# Power.net
KiCad netlist of a schematic drawn in Altium Designer
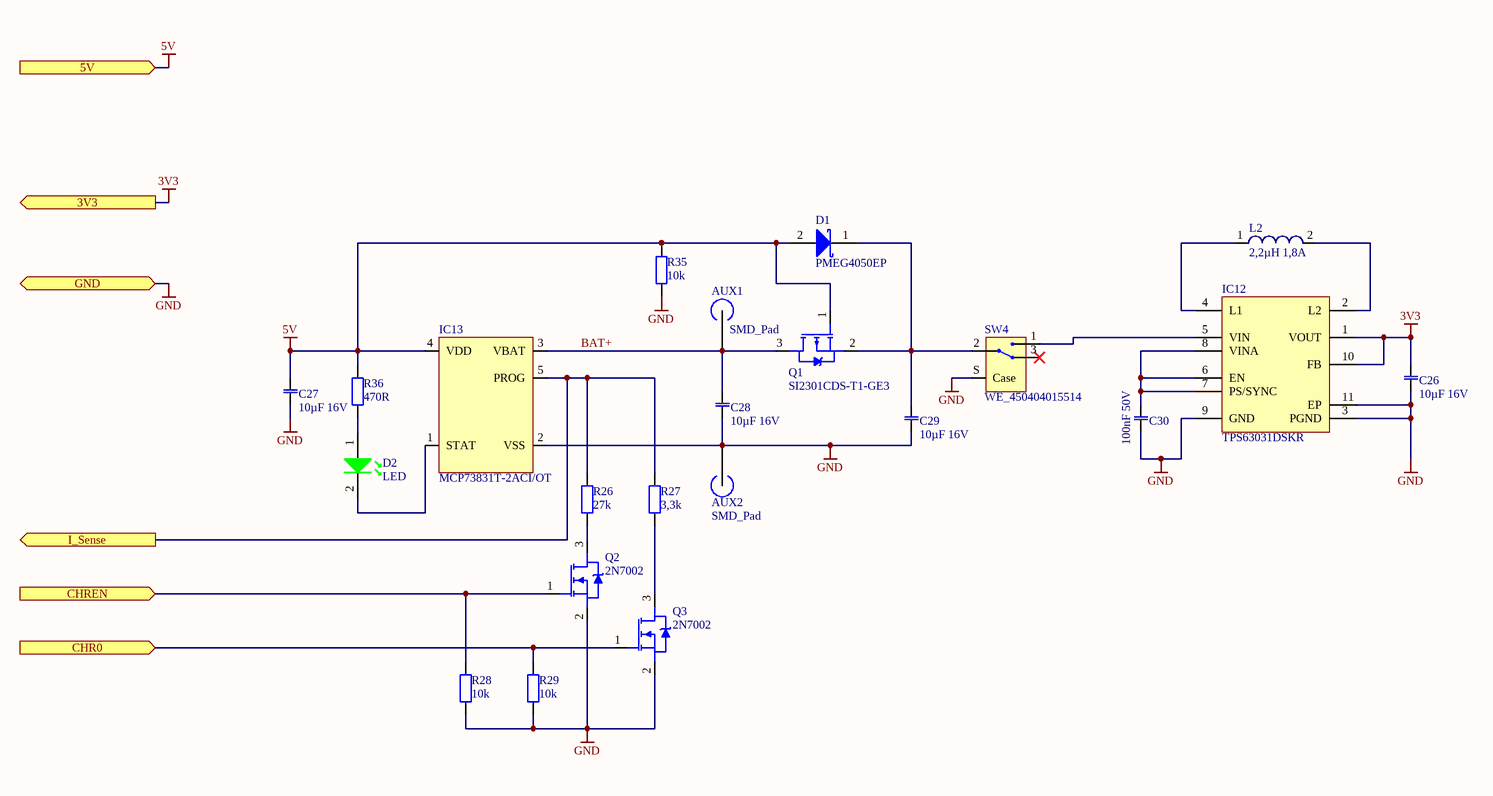
[diagram p0: Power.SchDoc]

(export (version "E")
  (design (tool "Eeschema 10.0.6"))
  (components
    (comp (ref "AUX1")
      (value "SMD_Pad")
      (footprint "SMD_PAD")
      (libsource (lib "iMAR Workspace") (part "AUX1"))
    )
    (comp (ref "AUX2")
      (value "SMD_Pad")
      (footprint "SMD_PAD")
      (libsource (lib "iMAR Workspace") (part "AUX1"))
    )
    (comp (ref "C26")
      (value "10µF 16V")
      (footprint "CAPC1608L")
      (description "10µF  16V  Ceramic  0603  10%  X5R")
      (fields (field (name "TOLERANCE") "10%") (field (name "MANUFACTURER") "unspecified"))
      (libsource (lib "iMAR Workspace") (part "Kondensator"))
    )
    (comp (ref "C27")
      (value "10µF 16V")
      (footprint "CAPC1608L")
      (description "10µF  16V  Ceramic  0603  10%  X5R")
      (fields (field (name "TOLERANCE") "10%") (field (name "MANUFACTURER") "unspecified"))
      (libsource (lib "iMAR Workspace") (part "Kondensator"))
    )
    (comp (ref "C28")
      (value "10µF 16V")
      (footprint "CAPC1608L")
      (description "10µF  16V  Ceramic  0603  10%  X5R")
      (fields (field (name "TOLERANCE") "10%") (field (name "MANUFACTURER") "unspecified"))
      (libsource (lib "iMAR Workspace") (part "Kondensator"))
    )
    (comp (ref "C29")
      (value "10µF 16V")
      (footprint "CAPC1608L")
      (description "10µF  16V  Ceramic  0603  10%  X5R")
      (fields (field (name "TOLERANCE") "10%") (field (name "MANUFACTURER") "unspecified"))
      (libsource (lib "iMAR Workspace") (part "Kondensator"))
    )
    (comp (ref "C30")
      (value "100nF 50V")
      (footprint "CAPC1005N")
      (description "100nF  50V  Ceramic  0402  10%  X7R")
      (fields (field (name "VOLTAGE") "50V") (field (name "MANUFACTURER") "unspecified"))
      (libsource (lib "iMAR Workspace") (part "Kondensator"))
    )
    (comp (ref "D1")
      (value "PMEG4050EP")
      (footprint "SOD4725X110")
      (description "Schottky-Diode 5A low Vf")
      (fields (field (name "MANUFACTURER") "NEXPERIA") (field (name "POWER") "625mW"))
      (libsource (lib "iMAR Workspace") (part "Schottky, A{colon}2, K{colon}1"))
    )
    (comp (ref "D2")
      (value "LED")
      (footprint "LEDM1608X11_Green")
      (description "LED green 0603 2,2V 20mA")
      (fields (field (name "MANUFACTURER") "KINGBRIGHT") (field (name "POWER") "62.5mW"))
      (libsource (lib "iMAR Workspace") (part "LED green"))
    )
    (comp (ref "IC12")
      (value "TPS63031DSKR")
      (footprint "SON50P250X80_HS-11N")
      (description "High Efficient Single Inductor Buck-Boost Converter with 1-A Switches")
      (fields (field (name "MANUFACTURER") "TEXAS INSTRUMENTS") (field (name "POWER") "1W"))
      (libsource (lib "iMAR Workspace") (part "TPS6303x"))
    )
    (comp (ref "IC13")
      (value "MCP73831T-2ACI/OT")
      (footprint "SOT95P275X110-5N")
      (description "Li-Polymer Charge Management Controller")
      (fields (field (name "MANUFACTURER") "MICROCHIP TECHNOLOGY"))
      (libsource (lib "iMAR Workspace") (part "MCP73831T-2ACI/OT"))
    )
    (comp (ref "L2")
      (value "2,2µH 1,8A")
      (footprint "IND_WE_TPC_2828")
      (description "WE-TPC  2,2µH  1,8A  2,4A  0,057R")
      (fields (field (name "MANUFACTURER") "WUERTH ELEKTRONIK"))
      (libsource (lib "iMAR Workspace") (part "Induktivitaet"))
    )
    (comp (ref "Q1")
      (value "SI2301CDS-T1-GE3")
      (footprint "SOT95P237X112-3N")
      (description "Leistungs-MOSFET, p-Kanal, 20 V, 3.1 A, 0.09 ohm, SOT-23, Oberflächenmontage")
      (fields (field (name "POWER") "1.6W") (field (name "MANUFACTURER") "VISHAY"))
      (libsource (lib "iMAR Workspace") (part "TRANS_MOSFET_P_E_3PIN"))
    )
    (comp (ref "Q2")
      (value "2N7002")
      (footprint "SOT95P237X100-3N")
      (description "Leistungs-MOSFET, n-Kanal, 60 V, 115 mA, 1.2 ohm, SOT-23, Oberflächenmontage")
      (fields (field (name "MANUFACTURER") "ON SEMICONDUCTOR") (field (name "POWER") "200mW"))
      (libsource (lib "iMAR Workspace") (part "TRANS_MOSFET_N_E_3PIN"))
    )
    (comp (ref "Q3")
      (value "2N7002")
      (footprint "SOT95P237X100-3N")
      (description "Leistungs-MOSFET, n-Kanal, 60 V, 115 mA, 1.2 ohm, SOT-23, Oberflächenmontage")
      (fields (field (name "MANUFACTURER") "ON SEMICONDUCTOR") (field (name "POWER") "200mW"))
      (libsource (lib "iMAR Workspace") (part "TRANS_MOSFET_N_E_3PIN"))
    )
    (comp (ref "R26")
      (value "27k")
      (footprint "RESC1005L")
      (description "27k  0402  62mW  1%  100ppm  50V")
      (fields (field (name "POWER") "62mW") (field (name "VOLTAGE") "50V"))
      (libsource (lib "") (part "Widerstand_1"))
    )
    (comp (ref "R27")
      (value "3,3k")
      (footprint "RESC1005L")
      (description "3,3k  0402  62mW  1%  100ppm  50V")
      (fields (field (name "POWER") "62mW") (field (name "MANUFACTURER") "unspecified"))
      (libsource (lib "iMAR Workspace") (part "Widerstand"))
    )
    (comp (ref "R28")
      (value "10k")
      (footprint "RESC1005L")
      (description "10k  0402  62mW  1%  100ppm  50V")
      (fields (field (name "MANUFACTURER") "unspecified") (field (name "POWER") "62mW"))
      (libsource (lib "iMAR Workspace") (part "Widerstand"))
    )
    (comp (ref "R29")
      (value "10k")
      (footprint "RESC1005L")
      (description "10k  0402  62mW  1%  100ppm  50V")
      (fields (field (name "MANUFACTURER") "unspecified") (field (name "POWER") "62mW"))
      (libsource (lib "iMAR Workspace") (part "Widerstand"))
    )
    (comp (ref "R35")
      (value "10k")
      (footprint "RESC1005L")
      (description "10k  0402  62mW  1%  100ppm  50V")
      (fields (field (name "MANUFACTURER") "unspecified") (field (name "POWER") "62mW"))
      (libsource (lib "iMAR Workspace") (part "Widerstand"))
    )
    (comp (ref "R36")
      (value "470R")
      (footprint "RESC1005L")
      (description "470R  0402  62mW  1%  100ppm  50V")
      (fields (field (name "POWER") "62mW") (field (name "MANUFACTURER") "unspecified"))
      (libsource (lib "iMAR Workspace") (part "Widerstand"))
    )
    (comp (ref "SW4")
      (value "WE_450404015514")
      (footprint "WE_450404015514")
      (description "WS-SLSU Mini Slide Switch")
      (fields (field (name "MANUFACTURER") "WUERTH ELEKTRONIK"))
      (libsource (lib "iMAR Workspace") (part "Schalter SPDT_S"))
    )
  )
  (nets
    (net (code "1") (name "/BAT+") (class "Default")
      (node (ref "AUX1") (pin "1") (pinfunction "1_1") (pintype "passive"))
      (node (ref "C28") (pin "2") (pinfunction "2_2") (pintype "passive"))
      (node (ref "IC13") (pin "3") (pinfunction "VBAT_3") (pintype "passive"))
      (node (ref "Q1") (pin "3") (pinfunction "D_3") (pintype "passive"))
    )
    (net (code "2") (name "/CHR0") (class "Default")
      (node (ref "Q3") (pin "1") (pinfunction "G_1") (pintype "passive"))
      (node (ref "R29") (pin "2") (pinfunction "2_2") (pintype "passive"))
    )
    (net (code "3") (name "/CHREN") (class "Default")
      (node (ref "Q2") (pin "1") (pinfunction "G_1") (pintype "passive"))
      (node (ref "R28") (pin "2") (pinfunction "2_2") (pintype "passive"))
    )
    (net (code "4") (name "/I_Sense") (class "Default")
      (node (ref "IC13") (pin "5") (pinfunction "PROG_5") (pintype "passive"))
      (node (ref "R26") (pin "1") (pinfunction "1_1") (pintype "passive"))
      (node (ref "R27") (pin "2") (pinfunction "2_2") (pintype "passive"))
    )
    (net (code "5") (name "3V3") (class "Default")
      (node (ref "C26") (pin "2") (pinfunction "2_2") (pintype "passive"))
      (node (ref "IC12") (pin "1") (pinfunction "VOUT_1") (pintype "passive"))
      (node (ref "IC12") (pin "10") (pinfunction "FB_10") (pintype "passive"))
    )
    (net (code "6") (name "5V") (class "Default")
      (node (ref "C27") (pin "2") (pinfunction "2_2") (pintype "passive"))
      (node (ref "D1") (pin "2") (pinfunction "A_2") (pintype "passive"))
      (node (ref "IC13") (pin "4") (pinfunction "VDD_4") (pintype "passive"))
      (node (ref "Q1") (pin "1") (pinfunction "G_1") (pintype "passive"))
      (node (ref "R35") (pin "2") (pinfunction "2_2") (pintype "passive"))
      (node (ref "R36") (pin "2") (pinfunction "2_2") (pintype "passive"))
    )
    (net (code "7") (name "GND") (class "Default")
      (node (ref "AUX2") (pin "1") (pinfunction "1_1") (pintype "passive"))
      (node (ref "C26") (pin "1") (pinfunction "1_1") (pintype "passive"))
      (node (ref "C27") (pin "1") (pinfunction "1_1") (pintype "passive"))
      (node (ref "C28") (pin "1") (pinfunction "1_1") (pintype "passive"))
      (node (ref "C29") (pin "1") (pinfunction "1_1") (pintype "passive"))
      (node (ref "C30") (pin "1") (pinfunction "1_1") (pintype "passive"))
      (node (ref "IC12") (pin "11") (pinfunction "EP_11") (pintype "passive"))
      (node (ref "IC12") (pin "3") (pinfunction "PGND_3") (pintype "passive"))
      (node (ref "IC12") (pin "9") (pinfunction "GND_9") (pintype "passive"))
      (node (ref "IC13") (pin "2") (pinfunction "VSS_2") (pintype "passive"))
      (node (ref "Q2") (pin "2") (pinfunction "S_2") (pintype "passive"))
      (node (ref "Q3") (pin "2") (pinfunction "S_2") (pintype "passive"))
      (node (ref "R28") (pin "1") (pinfunction "1_1") (pintype "passive"))
      (node (ref "R29") (pin "1") (pinfunction "1_1") (pintype "passive"))
      (node (ref "R35") (pin "1") (pinfunction "1_1") (pintype "passive"))
      (node (ref "SW4") (pin "S") (pinfunction "Case_S") (pintype "passive"))
    )
    (net (code "8") (name "Net-(D1-K)") (class "Default")
      (node (ref "C29") (pin "2") (pinfunction "2_2") (pintype "passive"))
      (node (ref "D1") (pin "1") (pinfunction "K_1") (pintype "passive"))
      (node (ref "Q1") (pin "2") (pinfunction "S_2") (pintype "passive"))
      (node (ref "SW4") (pin "2") (pinfunction "2_2") (pintype "passive"))
    )
    (net (code "9") (name "Net-(D2-Pad1)") (class "Default")
      (node (ref "D2") (pin "1") (pinfunction "1_1") (pintype "passive"))
      (node (ref "R36") (pin "1") (pinfunction "1_1") (pintype "passive"))
    )
    (net (code "10") (name "Net-(IC12-EN)") (class "Default")
      (node (ref "C30") (pin "2") (pinfunction "2_2") (pintype "passive"))
      (node (ref "IC12") (pin "6") (pinfunction "EN_6") (pintype "passive"))
      (node (ref "IC12") (pin "7") (pinfunction "PS/SYNC_7") (pintype "passive"))
      (node (ref "IC12") (pin "8") (pinfunction "VINA_8") (pintype "passive"))
    )
    (net (code "11") (name "Net-(IC12-L1)") (class "Default")
      (node (ref "IC12") (pin "4") (pinfunction "L1_4") (pintype "passive"))
      (node (ref "L2") (pin "1") (pinfunction "1_1") (pintype "passive"))
    )
    (net (code "12") (name "Net-(IC12-L2)") (class "Default")
      (node (ref "IC12") (pin "2") (pinfunction "L2_2") (pintype "passive"))
      (node (ref "L2") (pin "2") (pinfunction "2_2") (pintype "passive"))
    )
    (net (code "13") (name "Net-(IC12-VIN)") (class "Default")
      (node (ref "IC12") (pin "5") (pinfunction "VIN_5") (pintype "passive"))
      (node (ref "SW4") (pin "1") (pinfunction "1_1") (pintype "passive"))
    )
    (net (code "14") (name "Net-(IC13-STAT)") (class "Default")
      (node (ref "D2") (pin "2") (pinfunction "2_2") (pintype "passive"))
      (node (ref "IC13") (pin "1") (pinfunction "STAT_1") (pintype "passive"))
    )
    (net (code "15") (name "Net-(Q2-D)") (class "Default")
      (node (ref "Q2") (pin "3") (pinfunction "D_3") (pintype "passive"))
      (node (ref "R26") (pin "2") (pinfunction "2_2") (pintype "passive"))
    )
    (net (code "16") (name "Net-(Q3-D)") (class "Default")
      (node (ref "Q3") (pin "3") (pinfunction "D_3") (pintype "passive"))
      (node (ref "R27") (pin "1") (pinfunction "1_1") (pintype "passive"))
    )
    (net (code "17") (name "unconnected-(SW4-Pad3)") (class "Default")
      (node (ref "SW4") (pin "3") (pinfunction "3_3") (pintype "passive+no_connect"))
    )
  )
)
